# Qwiic_Distance_Sensor_-_VCNL4040.net
KiCad netlist of a schematic drawn in EAGLE
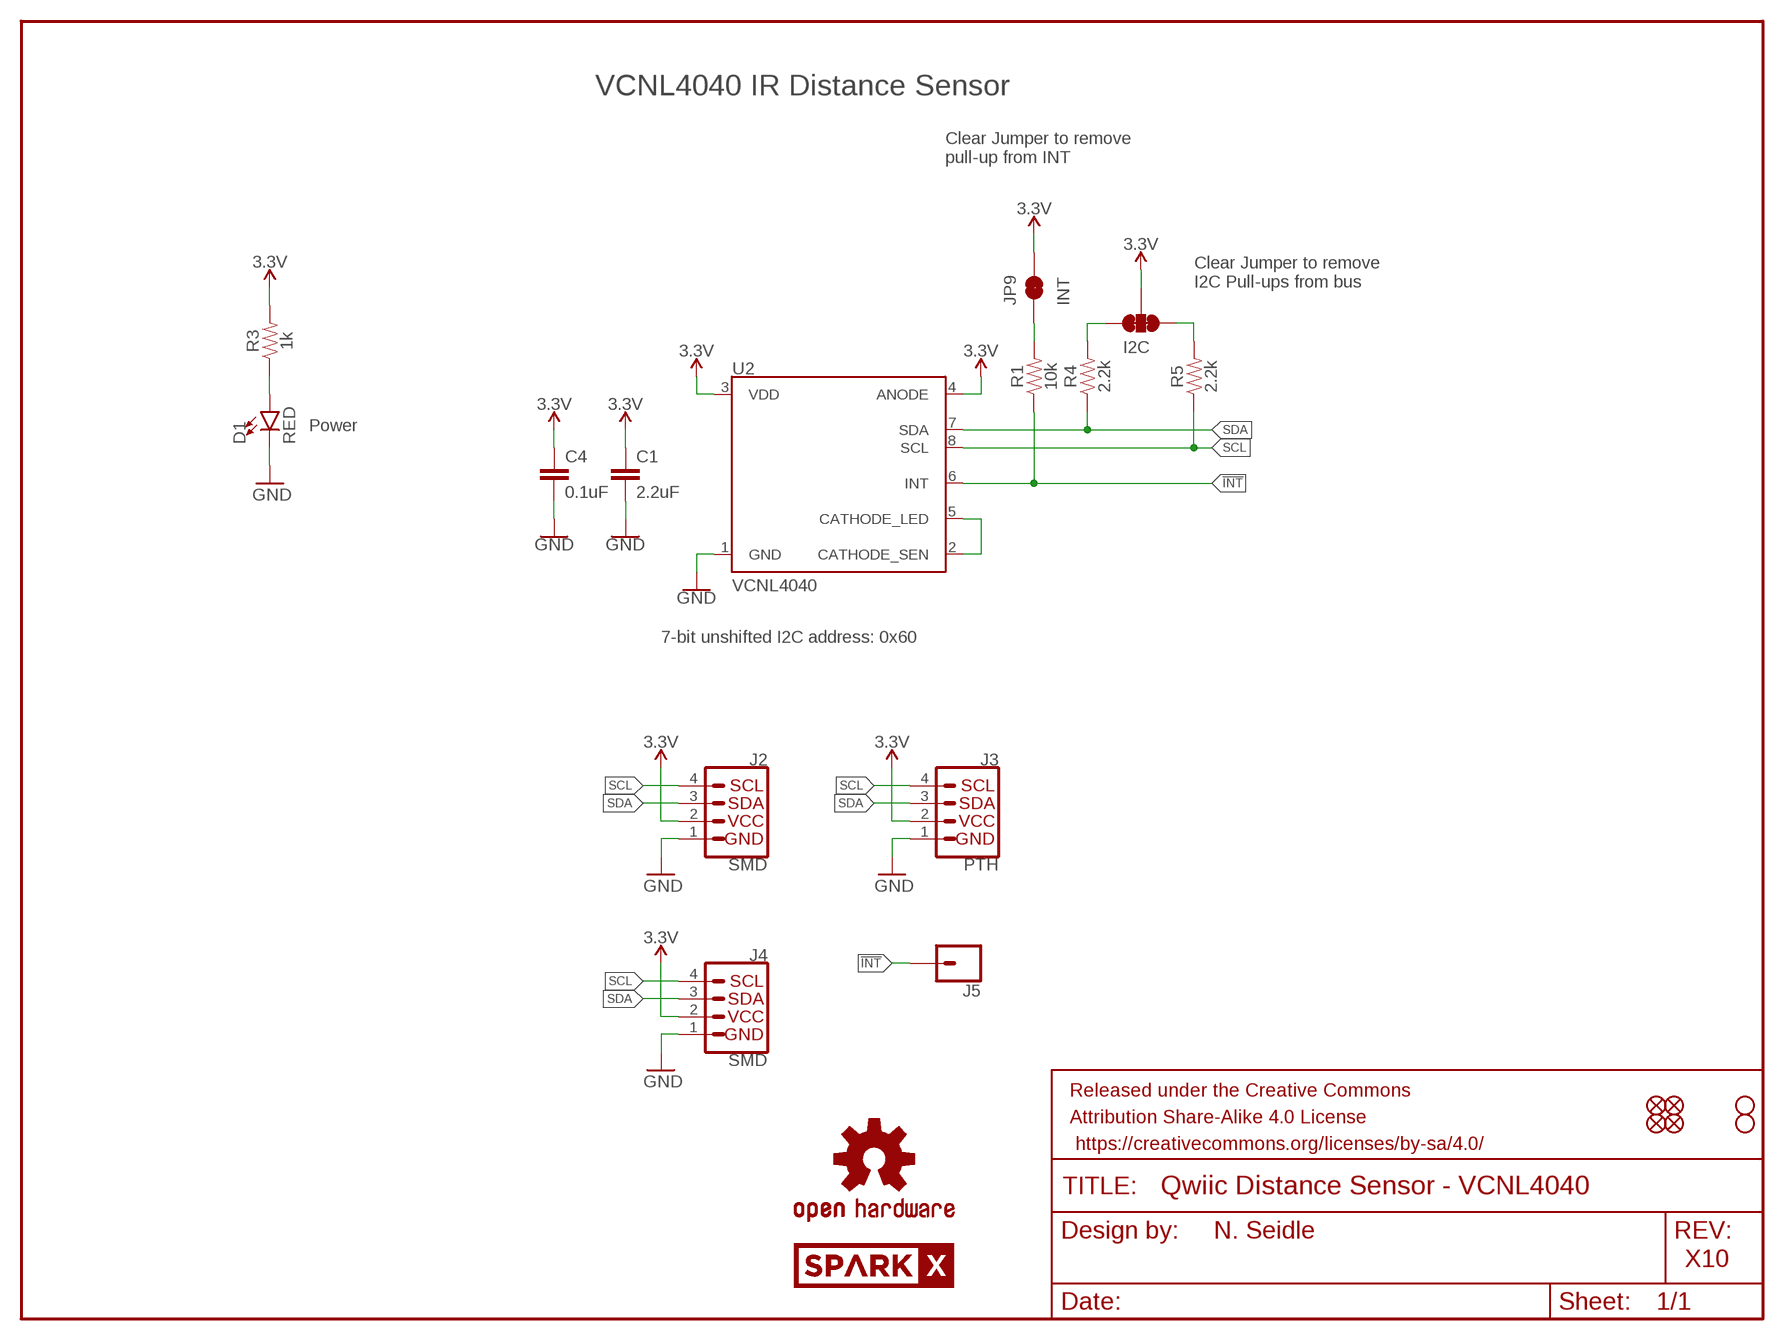
[diagram p0: schematic, sheet 1]

(export (version "E")
  (design (tool "Eeschema 10.0.6"))
  (components
    (comp (ref "C1")
      (value "2.2uF")
      (footprint "eagle-import:0603")
      (libsource (lib "eagle-import") (part "2.2UF-0603-10V-20%"))
    )
    (comp (ref "C4")
      (value "0.1uF")
      (footprint "eagle-import:0603")
      (libsource (lib "eagle-import") (part "0.1UF-0603-25V-(+80/-20%)"))
    )
    (comp (ref "D1")
      (value "RED")
      (footprint "eagle-import:LED-0603")
      (libsource (lib "eagle-import") (part "LED-RED0603"))
    )
    (comp (ref "FRAME1")
      (value "FRAME-LETTER")
      (footprint "eagle-import:CREATIVE_COMMONS")
      (libsource (lib "eagle-import") (part "FRAME-LETTER"))
    )
    (comp (ref "I2C")
      (value "JUMPER-SMT_3_2-NC_TRACE_SILK")
      (footprint "eagle-import:SMT-JUMPER_3_2-NC_TRACE_SILK")
      (libsource (lib "eagle-import") (part "JUMPER-SMT_3_2-NC_TRACE_SILK"))
    )
    (comp (ref "J2")
      (value "SMD")
      (footprint "eagle-import:1X04_1MM_RA")
      (libsource (lib "eagle-import") (part "I2C_STANDARDJS-1MM"))
    )
    (comp (ref "J3")
      (value "PTH")
      (footprint "eagle-import:1X04_NO_SILK")
      (libsource (lib "eagle-import") (part "I2C_STANDARD_NO_SILK"))
    )
    (comp (ref "J4")
      (value "SMD")
      (footprint "eagle-import:1X04_1MM_RA")
      (libsource (lib "eagle-import") (part "I2C_STANDARDJS-1MM"))
    )
    (comp (ref "J5")
      (value "CONN_01PTH_NO_SILK_YES_STOP")
      (footprint "eagle-import:1X01_NO_SILK")
      (libsource (lib "eagle-import") (part "CONN_01PTH_NO_SILK_YES_STOP"))
    )
    (comp (ref "JP1")
      (value "FIDUCIALUFIDUCIAL")
      (footprint "eagle-import:MICRO-FIDUCIAL")
      (libsource (lib "eagle-import") (part "FIDUCIALUFIDUCIAL"))
    )
    (comp (ref "JP2")
      (value "FIDUCIALUFIDUCIAL")
      (footprint "eagle-import:MICRO-FIDUCIAL")
      (libsource (lib "eagle-import") (part "FIDUCIALUFIDUCIAL"))
    )
    (comp (ref "JP3")
      (value "STAND-OFF")
      (footprint "eagle-import:STAND-OFF")
      (libsource (lib "eagle-import") (part "STAND-OFF"))
    )
    (comp (ref "JP4")
      (value "STAND-OFF")
      (footprint "eagle-import:STAND-OFF")
      (libsource (lib "eagle-import") (part "STAND-OFF"))
    )
    (comp (ref "JP5")
      (value "FIDUCIALUFIDUCIAL")
      (footprint "eagle-import:MICRO-FIDUCIAL")
      (libsource (lib "eagle-import") (part "FIDUCIALUFIDUCIAL"))
    )
    (comp (ref "JP6")
      (value "FIDUCIALUFIDUCIAL")
      (footprint "eagle-import:MICRO-FIDUCIAL")
      (libsource (lib "eagle-import") (part "FIDUCIALUFIDUCIAL"))
    )
    (comp (ref "JP9")
      (value "INT")
      (footprint "eagle-import:PAD-JUMPER-2-NC_BY_TRACE_YES_SILK")
      (libsource (lib "eagle-import") (part "JUMPER-PAD-2-NC_BY_TRACE"))
    )
    (comp (ref "LOGO1")
      (value "OSHW-LOGOMINI")
      (footprint "eagle-import:OSHW-LOGO-MINI")
      (libsource (lib "eagle-import") (part "OSHW-LOGOMINI"))
    )
    (comp (ref "R1")
      (value "10k")
      (footprint "eagle-import:0603")
      (libsource (lib "eagle-import") (part "10KOHM-0603-1/10W-1%"))
    )
    (comp (ref "R3")
      (value "1k")
      (footprint "eagle-import:0603")
      (libsource (lib "eagle-import") (part "1KOHM-0603-1/10W-1%"))
    )
    (comp (ref "R4")
      (value "2.2k")
      (footprint "eagle-import:0603")
      (libsource (lib "eagle-import") (part "2.2KOHM-0603-1/10W-1%"))
    )
    (comp (ref "R5")
      (value "2.2k")
      (footprint "eagle-import:0603")
      (libsource (lib "eagle-import") (part "2.2KOHM-0603-1/10W-1%"))
    )
    (comp (ref "U$1")
      (value "SPARKX-LOGO4")
      (footprint "eagle-import:SPARKX-MEDIUM")
      (libsource (lib "eagle-import") (part "SPARKX-LOGO4"))
    )
    (comp (ref "U$2")
      (value "SPARKX-LOGO4")
      (footprint "eagle-import:SPARKX-MEDIUM")
      (libsource (lib "eagle-import") (part "SPARKX-LOGO4"))
    )
    (comp (ref "U2")
      (value "VCNL4040")
      (footprint "eagle-import:VCNL4040")
      (libsource (lib "eagle-import") (part "VCNL4040"))
    )
  )
  (nets
    (net (code "1") (name "/~{INT}") (class "Default")
      (node (ref "J5") (pin "1") (pinfunction "1_1") (pintype "passive"))
      (node (ref "R1") (pin "1") (pinfunction "1_1") (pintype "passive"))
      (node (ref "U2") (pin "6") (pinfunction "INT_6") (pintype "bidirectional"))
    )
    (net (code "2") (name "3.3V") (class "Default")
      (node (ref "C1") (pin "1") (pinfunction "1_1") (pintype "passive"))
      (node (ref "C4") (pin "1") (pinfunction "1_1") (pintype "passive"))
      (node (ref "I2C") (pin "2") (pinfunction "2_2") (pintype "passive"))
      (node (ref "J2") (pin "2") (pinfunction "VCC_2") (pintype "power_in"))
      (node (ref "J3") (pin "2") (pinfunction "VCC_2") (pintype "power_in"))
      (node (ref "J4") (pin "2") (pinfunction "VCC_2") (pintype "power_in"))
      (node (ref "JP9") (pin "2") (pinfunction "2_2") (pintype "passive"))
      (node (ref "R3") (pin "2") (pinfunction "2_2") (pintype "passive"))
      (node (ref "U2") (pin "3") (pinfunction "VDD_3") (pintype "bidirectional"))
      (node (ref "U2") (pin "4") (pinfunction "ANODE_4") (pintype "bidirectional"))
    )
    (net (code "3") (name "GND") (class "Default")
      (node (ref "C1") (pin "2") (pinfunction "2_2") (pintype "passive"))
      (node (ref "C4") (pin "2") (pinfunction "2_2") (pintype "passive"))
      (node (ref "D1") (pin "C") (pinfunction "C_C") (pintype "passive"))
      (node (ref "J2") (pin "1") (pinfunction "GND_1") (pintype "power_in"))
      (node (ref "J3") (pin "1") (pinfunction "GND_1") (pintype "power_in"))
      (node (ref "J4") (pin "1") (pinfunction "GND_1") (pintype "power_in"))
      (node (ref "U2") (pin "1") (pinfunction "GND_1") (pintype "bidirectional"))
    )
    (net (code "4") (name "Net-(D1-PadA)") (class "Default")
      (node (ref "D1") (pin "A") (pinfunction "A_A") (pintype "passive"))
      (node (ref "R3") (pin "1") (pinfunction "1_1") (pintype "passive"))
    )
    (net (code "5") (name "Net-(I2C-Pad1)") (class "Default")
      (node (ref "I2C") (pin "1") (pinfunction "1_1") (pintype "passive"))
      (node (ref "R5") (pin "2") (pinfunction "2_2") (pintype "passive"))
    )
    (net (code "6") (name "Net-(I2C-Pad3)") (class "Default")
      (node (ref "I2C") (pin "3") (pinfunction "3_3") (pintype "passive"))
      (node (ref "R4") (pin "2") (pinfunction "2_2") (pintype "passive"))
    )
    (net (code "7") (name "Net-(JP9-Pad1)") (class "Default")
      (node (ref "JP9") (pin "1") (pinfunction "1_1") (pintype "passive"))
      (node (ref "R1") (pin "2") (pinfunction "2_2") (pintype "passive"))
    )
    (net (code "8") (name "Net-(U2-CATHODE_LED)") (class "Default")
      (node (ref "U2") (pin "2") (pinfunction "CATHODE_SEN_2") (pintype "bidirectional"))
      (node (ref "U2") (pin "5") (pinfunction "CATHODE_LED_5") (pintype "bidirectional"))
    )
    (net (code "9") (name "SCL") (class "Default")
      (node (ref "J2") (pin "4") (pinfunction "SCL_4") (pintype "passive"))
      (node (ref "J3") (pin "4") (pinfunction "SCL_4") (pintype "passive"))
      (node (ref "J4") (pin "4") (pinfunction "SCL_4") (pintype "passive"))
      (node (ref "R5") (pin "1") (pinfunction "1_1") (pintype "passive"))
      (node (ref "U2") (pin "8") (pinfunction "SCL_8") (pintype "bidirectional"))
    )
    (net (code "10") (name "SDA") (class "Default")
      (node (ref "J2") (pin "3") (pinfunction "SDA_3") (pintype "passive"))
      (node (ref "J3") (pin "3") (pinfunction "SDA_3") (pintype "passive"))
      (node (ref "J4") (pin "3") (pinfunction "SDA_3") (pintype "passive"))
      (node (ref "R4") (pin "1") (pinfunction "1_1") (pintype "passive"))
      (node (ref "U2") (pin "7") (pinfunction "SDA_7") (pintype "bidirectional"))
    )
  )
)
